# what-tinys-it.net
KiCad netlist of a schematic drawn in EAGLE
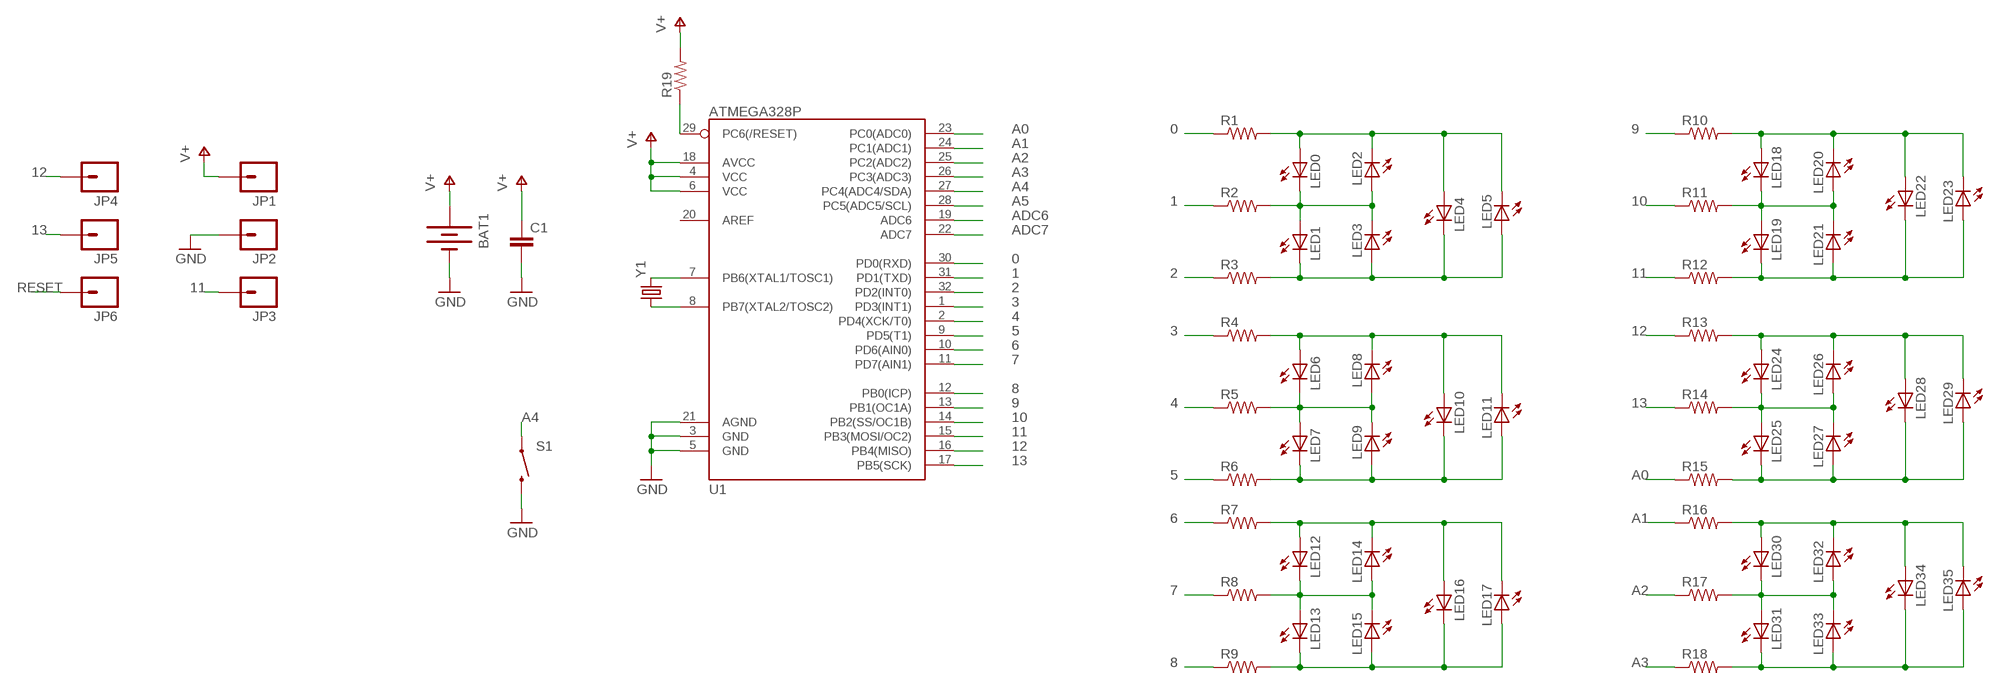
[diagram p0: schematic, sheet 1]

(export (version "E")
  (design (tool "Eeschema 10.0.6"))
  (components
    (comp (ref "BAT1")
      (value "BATTERY20SMD")
      (footprint "eagle-import:BATTCON_20MM")
      (libsource (lib "eagle-import") (part "BATTERY20SMD"))
    )
    (comp (ref "C1")
      (value "C-EUC0805")
      (footprint "eagle-import:C0805")
      (libsource (lib "eagle-import") (part "C-EUC0805"))
    )
    (comp (ref "JP1")
      (value "M01SMDNS")
      (footprint "eagle-import:1X01NS")
      (libsource (lib "eagle-import") (part "M01SMDNS"))
    )
    (comp (ref "JP2")
      (value "M01SMDNS")
      (footprint "eagle-import:1X01NS")
      (libsource (lib "eagle-import") (part "M01SMDNS"))
    )
    (comp (ref "JP3")
      (value "M01SMDNS")
      (footprint "eagle-import:1X01NS")
      (libsource (lib "eagle-import") (part "M01SMDNS"))
    )
    (comp (ref "JP4")
      (value "M01SMDNS")
      (footprint "eagle-import:1X01NS")
      (libsource (lib "eagle-import") (part "M01SMDNS"))
    )
    (comp (ref "JP5")
      (value "M01SMDNS")
      (footprint "eagle-import:1X01NS")
      (libsource (lib "eagle-import") (part "M01SMDNS"))
    )
    (comp (ref "JP6")
      (value "M01SMDNS")
      (footprint "eagle-import:1X01NS")
      (libsource (lib "eagle-import") (part "M01SMDNS"))
    )
    (comp (ref "LED0")
      (value "LEDCHIPLED_0805")
      (footprint "eagle-import:CHIPLED_0805")
      (libsource (lib "eagle-import") (part "LEDCHIPLED_0805"))
    )
    (comp (ref "LED1")
      (value "LEDCHIPLED_0805")
      (footprint "eagle-import:CHIPLED_0805")
      (libsource (lib "eagle-import") (part "LEDCHIPLED_0805"))
    )
    (comp (ref "LED2")
      (value "LEDCHIPLED_0805")
      (footprint "eagle-import:CHIPLED_0805")
      (libsource (lib "eagle-import") (part "LEDCHIPLED_0805"))
    )
    (comp (ref "LED3")
      (value "LEDCHIPLED_0805")
      (footprint "eagle-import:CHIPLED_0805")
      (libsource (lib "eagle-import") (part "LEDCHIPLED_0805"))
    )
    (comp (ref "LED4")
      (value "LEDCHIPLED_0805")
      (footprint "eagle-import:CHIPLED_0805")
      (libsource (lib "eagle-import") (part "LEDCHIPLED_0805"))
    )
    (comp (ref "LED5")
      (value "LEDCHIPLED_0805")
      (footprint "eagle-import:CHIPLED_0805")
      (libsource (lib "eagle-import") (part "LEDCHIPLED_0805"))
    )
    (comp (ref "LED6")
      (value "LEDCHIPLED_0805")
      (footprint "eagle-import:CHIPLED_0805")
      (libsource (lib "eagle-import") (part "LEDCHIPLED_0805"))
    )
    (comp (ref "LED7")
      (value "LEDCHIPLED_0805")
      (footprint "eagle-import:CHIPLED_0805")
      (libsource (lib "eagle-import") (part "LEDCHIPLED_0805"))
    )
    (comp (ref "LED8")
      (value "LEDCHIPLED_0805")
      (footprint "eagle-import:CHIPLED_0805")
      (libsource (lib "eagle-import") (part "LEDCHIPLED_0805"))
    )
    (comp (ref "LED9")
      (value "LEDCHIPLED_0805")
      (footprint "eagle-import:CHIPLED_0805")
      (libsource (lib "eagle-import") (part "LEDCHIPLED_0805"))
    )
    (comp (ref "LED10")
      (value "LEDCHIPLED_0805")
      (footprint "eagle-import:CHIPLED_0805")
      (libsource (lib "eagle-import") (part "LEDCHIPLED_0805"))
    )
    (comp (ref "LED11")
      (value "LEDCHIPLED_0805")
      (footprint "eagle-import:CHIPLED_0805")
      (libsource (lib "eagle-import") (part "LEDCHIPLED_0805"))
    )
    (comp (ref "LED12")
      (value "LEDCHIPLED_0805")
      (footprint "eagle-import:CHIPLED_0805")
      (libsource (lib "eagle-import") (part "LEDCHIPLED_0805"))
    )
    (comp (ref "LED13")
      (value "LEDCHIPLED_0805")
      (footprint "eagle-import:CHIPLED_0805")
      (libsource (lib "eagle-import") (part "LEDCHIPLED_0805"))
    )
    (comp (ref "LED14")
      (value "LEDCHIPLED_0805")
      (footprint "eagle-import:CHIPLED_0805")
      (libsource (lib "eagle-import") (part "LEDCHIPLED_0805"))
    )
    (comp (ref "LED15")
      (value "LEDCHIPLED_0805")
      (footprint "eagle-import:CHIPLED_0805")
      (libsource (lib "eagle-import") (part "LEDCHIPLED_0805"))
    )
    (comp (ref "LED16")
      (value "LEDCHIPLED_0805")
      (footprint "eagle-import:CHIPLED_0805")
      (libsource (lib "eagle-import") (part "LEDCHIPLED_0805"))
    )
    (comp (ref "LED17")
      (value "LEDCHIPLED_0805")
      (footprint "eagle-import:CHIPLED_0805")
      (libsource (lib "eagle-import") (part "LEDCHIPLED_0805"))
    )
    (comp (ref "LED18")
      (value "LEDCHIPLED_0805")
      (footprint "eagle-import:CHIPLED_0805")
      (libsource (lib "eagle-import") (part "LEDCHIPLED_0805"))
    )
    (comp (ref "LED19")
      (value "LEDCHIPLED_0805")
      (footprint "eagle-import:CHIPLED_0805")
      (libsource (lib "eagle-import") (part "LEDCHIPLED_0805"))
    )
    (comp (ref "LED20")
      (value "LEDCHIPLED_0805")
      (footprint "eagle-import:CHIPLED_0805")
      (libsource (lib "eagle-import") (part "LEDCHIPLED_0805"))
    )
    (comp (ref "LED21")
      (value "LEDCHIPLED_0805")
      (footprint "eagle-import:CHIPLED_0805")
      (libsource (lib "eagle-import") (part "LEDCHIPLED_0805"))
    )
    (comp (ref "LED22")
      (value "LEDCHIPLED_0805")
      (footprint "eagle-import:CHIPLED_0805")
      (libsource (lib "eagle-import") (part "LEDCHIPLED_0805"))
    )
    (comp (ref "LED23")
      (value "LEDCHIPLED_0805")
      (footprint "eagle-import:CHIPLED_0805")
      (libsource (lib "eagle-import") (part "LEDCHIPLED_0805"))
    )
    (comp (ref "LED24")
      (value "LEDCHIPLED_0805")
      (footprint "eagle-import:CHIPLED_0805")
      (libsource (lib "eagle-import") (part "LEDCHIPLED_0805"))
    )
    (comp (ref "LED25")
      (value "LEDCHIPLED_0805")
      (footprint "eagle-import:CHIPLED_0805")
      (libsource (lib "eagle-import") (part "LEDCHIPLED_0805"))
    )
    (comp (ref "LED26")
      (value "LEDCHIPLED_0805")
      (footprint "eagle-import:CHIPLED_0805")
      (libsource (lib "eagle-import") (part "LEDCHIPLED_0805"))
    )
    (comp (ref "LED27")
      (value "LEDCHIPLED_0805")
      (footprint "eagle-import:CHIPLED_0805")
      (libsource (lib "eagle-import") (part "LEDCHIPLED_0805"))
    )
    (comp (ref "LED28")
      (value "LEDCHIPLED_0805")
      (footprint "eagle-import:CHIPLED_0805")
      (libsource (lib "eagle-import") (part "LEDCHIPLED_0805"))
    )
    (comp (ref "LED29")
      (value "LEDCHIPLED_0805")
      (footprint "eagle-import:CHIPLED_0805")
      (libsource (lib "eagle-import") (part "LEDCHIPLED_0805"))
    )
    (comp (ref "LED30")
      (value "LEDCHIPLED_0805")
      (footprint "eagle-import:CHIPLED_0805")
      (libsource (lib "eagle-import") (part "LEDCHIPLED_0805"))
    )
    (comp (ref "LED31")
      (value "LEDCHIPLED_0805")
      (footprint "eagle-import:CHIPLED_0805")
      (libsource (lib "eagle-import") (part "LEDCHIPLED_0805"))
    )
    (comp (ref "LED32")
      (value "LEDCHIPLED_0805")
      (footprint "eagle-import:CHIPLED_0805")
      (libsource (lib "eagle-import") (part "LEDCHIPLED_0805"))
    )
    (comp (ref "LED33")
      (value "LEDCHIPLED_0805")
      (footprint "eagle-import:CHIPLED_0805")
      (libsource (lib "eagle-import") (part "LEDCHIPLED_0805"))
    )
    (comp (ref "LED34")
      (value "LEDCHIPLED_0805")
      (footprint "eagle-import:CHIPLED_0805")
      (libsource (lib "eagle-import") (part "LEDCHIPLED_0805"))
    )
    (comp (ref "LED35")
      (value "LEDCHIPLED_0805")
      (footprint "eagle-import:CHIPLED_0805")
      (libsource (lib "eagle-import") (part "LEDCHIPLED_0805"))
    )
    (comp (ref "R1")
      (value "RESISTOR0805-RES")
      (footprint "eagle-import:0805")
      (libsource (lib "eagle-import") (part "RESISTOR0805-RES"))
    )
    (comp (ref "R2")
      (value "RESISTOR0805-RES")
      (footprint "eagle-import:0805")
      (libsource (lib "eagle-import") (part "RESISTOR0805-RES"))
    )
    (comp (ref "R3")
      (value "RESISTOR0805-RES")
      (footprint "eagle-import:0805")
      (libsource (lib "eagle-import") (part "RESISTOR0805-RES"))
    )
    (comp (ref "R4")
      (value "RESISTOR0805-RES")
      (footprint "eagle-import:0805")
      (libsource (lib "eagle-import") (part "RESISTOR0805-RES"))
    )
    (comp (ref "R5")
      (value "RESISTOR0805-RES")
      (footprint "eagle-import:0805")
      (libsource (lib "eagle-import") (part "RESISTOR0805-RES"))
    )
    (comp (ref "R6")
      (value "RESISTOR0805-RES")
      (footprint "eagle-import:0805")
      (libsource (lib "eagle-import") (part "RESISTOR0805-RES"))
    )
    (comp (ref "R7")
      (value "RESISTOR0805-RES")
      (footprint "eagle-import:0805")
      (libsource (lib "eagle-import") (part "RESISTOR0805-RES"))
    )
    (comp (ref "R8")
      (value "RESISTOR0805-RES")
      (footprint "eagle-import:0805")
      (libsource (lib "eagle-import") (part "RESISTOR0805-RES"))
    )
    (comp (ref "R9")
      (value "RESISTOR0805-RES")
      (footprint "eagle-import:0805")
      (libsource (lib "eagle-import") (part "RESISTOR0805-RES"))
    )
    (comp (ref "R10")
      (value "RESISTOR0805-RES")
      (footprint "eagle-import:0805")
      (libsource (lib "eagle-import") (part "RESISTOR0805-RES"))
    )
    (comp (ref "R11")
      (value "RESISTOR0805-RES")
      (footprint "eagle-import:0805")
      (libsource (lib "eagle-import") (part "RESISTOR0805-RES"))
    )
    (comp (ref "R12")
      (value "RESISTOR0805-RES")
      (footprint "eagle-import:0805")
      (libsource (lib "eagle-import") (part "RESISTOR0805-RES"))
    )
    (comp (ref "R13")
      (value "RESISTOR0805-RES")
      (footprint "eagle-import:0805")
      (libsource (lib "eagle-import") (part "RESISTOR0805-RES"))
    )
    (comp (ref "R14")
      (value "RESISTOR0805-RES")
      (footprint "eagle-import:0805")
      (libsource (lib "eagle-import") (part "RESISTOR0805-RES"))
    )
    (comp (ref "R15")
      (value "RESISTOR0805-RES")
      (footprint "eagle-import:0805")
      (libsource (lib "eagle-import") (part "RESISTOR0805-RES"))
    )
    (comp (ref "R16")
      (value "RESISTOR0805-RES")
      (footprint "eagle-import:0805")
      (libsource (lib "eagle-import") (part "RESISTOR0805-RES"))
    )
    (comp (ref "R17")
      (value "RESISTOR0805-RES")
      (footprint "eagle-import:0805")
      (libsource (lib "eagle-import") (part "RESISTOR0805-RES"))
    )
    (comp (ref "R18")
      (value "RESISTOR0805-RES")
      (footprint "eagle-import:0805")
      (libsource (lib "eagle-import") (part "RESISTOR0805-RES"))
    )
    (comp (ref "R19")
      (value "RESISTOR0805-RES")
      (footprint "eagle-import:0805")
      (libsource (lib "eagle-import") (part "RESISTOR0805-RES"))
    )
    (comp (ref "S1")
      (value "SWITCH-MOMENTARY-2SMD-3")
      (footprint "eagle-import:TACTILE_SWITCH_SMD-3")
      (libsource (lib "eagle-import") (part "SWITCH-MOMENTARY-2SMD-3"))
    )
    (comp (ref "U1")
      (value "ATMEGA328P")
      (footprint "eagle-import:TQFP32-08")
      (libsource (lib "eagle-import") (part "ATMEGA328_SMT"))
    )
    (comp (ref "Y1")
      (value "CRYSTAL32-SMD")
      (footprint "eagle-import:CRYSTAL-32KHZ-SMD")
      (libsource (lib "eagle-import") (part "CRYSTAL32-SMD"))
    )
  )
  (nets
    (net (code "1") (name "/0") (class "Default")
      (node (ref "R1") (pin "1") (pinfunction "1_1") (pintype "passive"))
      (node (ref "U1") (pin "30") (pinfunction "PD0(RXD)_30") (pintype "bidirectional"))
    )
    (net (code "2") (name "/1") (class "Default")
      (node (ref "R2") (pin "1") (pinfunction "1_1") (pintype "passive"))
      (node (ref "U1") (pin "31") (pinfunction "PD1(TXD)_31") (pintype "bidirectional"))
    )
    (net (code "3") (name "/2") (class "Default")
      (node (ref "R3") (pin "1") (pinfunction "1_1") (pintype "passive"))
      (node (ref "U1") (pin "32") (pinfunction "PD2(INT0)_32") (pintype "bidirectional"))
    )
    (net (code "4") (name "/3") (class "Default")
      (node (ref "R4") (pin "1") (pinfunction "1_1") (pintype "passive"))
      (node (ref "U1") (pin "1") (pinfunction "PD3(INT1)_1") (pintype "bidirectional"))
    )
    (net (code "5") (name "/4") (class "Default")
      (node (ref "R5") (pin "1") (pinfunction "1_1") (pintype "passive"))
      (node (ref "U1") (pin "2") (pinfunction "PD4(XCK/T0)_2") (pintype "bidirectional"))
    )
    (net (code "6") (name "/5") (class "Default")
      (node (ref "R6") (pin "1") (pinfunction "1_1") (pintype "passive"))
      (node (ref "U1") (pin "9") (pinfunction "PD5(T1)_9") (pintype "bidirectional"))
    )
    (net (code "7") (name "/6") (class "Default")
      (node (ref "R7") (pin "1") (pinfunction "1_1") (pintype "passive"))
      (node (ref "U1") (pin "10") (pinfunction "PD6(AIN0)_10") (pintype "bidirectional"))
    )
    (net (code "8") (name "/7") (class "Default")
      (node (ref "R8") (pin "1") (pinfunction "1_1") (pintype "passive"))
      (node (ref "U1") (pin "11") (pinfunction "PD7(AIN1)_11") (pintype "bidirectional"))
    )
    (net (code "9") (name "/8") (class "Default")
      (node (ref "R9") (pin "1") (pinfunction "1_1") (pintype "passive"))
      (node (ref "U1") (pin "12") (pinfunction "PB0(ICP)_12") (pintype "bidirectional"))
    )
    (net (code "10") (name "/9") (class "Default")
      (node (ref "R10") (pin "1") (pinfunction "1_1") (pintype "passive"))
      (node (ref "U1") (pin "13") (pinfunction "PB1(OC1A)_13") (pintype "bidirectional"))
    )
    (net (code "11") (name "/10") (class "Default")
      (node (ref "R11") (pin "1") (pinfunction "1_1") (pintype "passive"))
      (node (ref "U1") (pin "14") (pinfunction "PB2(SS/OC1B)_14") (pintype "bidirectional"))
    )
    (net (code "12") (name "/11") (class "Default")
      (node (ref "JP3") (pin "1") (pinfunction "1_1") (pintype "passive"))
      (node (ref "R12") (pin "1") (pinfunction "1_1") (pintype "passive"))
      (node (ref "U1") (pin "15") (pinfunction "PB3(MOSI/OC2)_15") (pintype "bidirectional"))
    )
    (net (code "13") (name "/12") (class "Default")
      (node (ref "JP4") (pin "1") (pinfunction "1_1") (pintype "passive"))
      (node (ref "R13") (pin "1") (pinfunction "1_1") (pintype "passive"))
      (node (ref "U1") (pin "16") (pinfunction "PB4(MISO)_16") (pintype "bidirectional"))
    )
    (net (code "14") (name "/13") (class "Default")
      (node (ref "JP5") (pin "1") (pinfunction "1_1") (pintype "passive"))
      (node (ref "R14") (pin "1") (pinfunction "1_1") (pintype "passive"))
      (node (ref "U1") (pin "17") (pinfunction "PB5(SCK)_17") (pintype "bidirectional"))
    )
    (net (code "15") (name "/A0") (class "Default")
      (node (ref "R15") (pin "1") (pinfunction "1_1") (pintype "passive"))
      (node (ref "U1") (pin "23") (pinfunction "PC0(ADC0)_23") (pintype "bidirectional"))
    )
    (net (code "16") (name "/A1") (class "Default")
      (node (ref "R16") (pin "1") (pinfunction "1_1") (pintype "passive"))
      (node (ref "U1") (pin "24") (pinfunction "PC1(ADC1)_24") (pintype "bidirectional"))
    )
    (net (code "17") (name "/A2") (class "Default")
      (node (ref "R17") (pin "1") (pinfunction "1_1") (pintype "passive"))
      (node (ref "U1") (pin "25") (pinfunction "PC2(ADC2)_25") (pintype "bidirectional"))
    )
    (net (code "18") (name "/A3") (class "Default")
      (node (ref "R18") (pin "1") (pinfunction "1_1") (pintype "passive"))
      (node (ref "U1") (pin "26") (pinfunction "PC3(ADC3)_26") (pintype "bidirectional"))
    )
    (net (code "19") (name "/A4") (class "Default")
      (node (ref "S1") (pin "1") (pinfunction "1_1") (pintype "passive"))
      (node (ref "U1") (pin "27") (pinfunction "PC4(ADC4/SDA)_27") (pintype "bidirectional"))
    )
    (net (code "20") (name "/A5") (class "Default")
      (node (ref "U1") (pin "28") (pinfunction "PC5(ADC5/SCL)_28") (pintype "bidirectional"))
    )
    (net (code "21") (name "/ADC6") (class "Default")
      (node (ref "U1") (pin "19") (pinfunction "ADC6_19") (pintype "bidirectional"))
    )
    (net (code "22") (name "/ADC7") (class "Default")
      (node (ref "U1") (pin "22") (pinfunction "ADC7_22") (pintype "bidirectional"))
    )
    (net (code "23") (name "/RESET") (class "Default")
      (node (ref "JP6") (pin "1") (pinfunction "1_1") (pintype "passive"))
      (node (ref "R19") (pin "1") (pinfunction "1_1") (pintype "passive"))
      (node (ref "U1") (pin "29") (pinfunction "PC6(/RESET)_29") (pintype "bidirectional"))
    )
    (net (code "24") (name "GND") (class "Default")
      (node (ref "BAT1") (pin "2") (pinfunction "-_2") (pintype "power_in"))
      (node (ref "C1") (pin "2") (pinfunction "2_2") (pintype "passive"))
      (node (ref "JP2") (pin "1") (pinfunction "1_1") (pintype "passive"))
      (node (ref "S1") (pin "4") (pinfunction "2_4") (pintype "passive"))
      (node (ref "U1") (pin "21") (pinfunction "AGND_21") (pintype "bidirectional"))
      (node (ref "U1") (pin "3") (pinfunction "GND_3") (pintype "bidirectional"))
      (node (ref "U1") (pin "5") (pinfunction "GND_5") (pintype "bidirectional"))
    )
    (net (code "25") (name "Net-(LED0-PadA)") (class "Default")
      (node (ref "LED0") (pin "A") (pinfunction "A_A") (pintype "passive"))
      (node (ref "LED2") (pin "C") (pinfunction "C_C") (pintype "passive"))
      (node (ref "LED4") (pin "A") (pinfunction "A_A") (pintype "passive"))
      (node (ref "LED5") (pin "C") (pinfunction "C_C") (pintype "passive"))
      (node (ref "R1") (pin "2") (pinfunction "2_2") (pintype "passive"))
    )
    (net (code "26") (name "Net-(LED0-PadC)") (class "Default")
      (node (ref "LED0") (pin "C") (pinfunction "C_C") (pintype "passive"))
      (node (ref "LED1") (pin "A") (pinfunction "A_A") (pintype "passive"))
      (node (ref "LED2") (pin "A") (pinfunction "A_A") (pintype "passive"))
      (node (ref "LED3") (pin "C") (pinfunction "C_C") (pintype "passive"))
      (node (ref "R2") (pin "2") (pinfunction "2_2") (pintype "passive"))
    )
    (net (code "27") (name "Net-(LED1-PadC)") (class "Default")
      (node (ref "LED1") (pin "C") (pinfunction "C_C") (pintype "passive"))
      (node (ref "LED3") (pin "A") (pinfunction "A_A") (pintype "passive"))
      (node (ref "LED4") (pin "C") (pinfunction "C_C") (pintype "passive"))
      (node (ref "LED5") (pin "A") (pinfunction "A_A") (pintype "passive"))
      (node (ref "R3") (pin "2") (pinfunction "2_2") (pintype "passive"))
    )
    (net (code "28") (name "Net-(LED6-PadC)") (class "Default")
      (node (ref "LED6") (pin "C") (pinfunction "C_C") (pintype "passive"))
      (node (ref "LED7") (pin "A") (pinfunction "A_A") (pintype "passive"))
      (node (ref "LED8") (pin "A") (pinfunction "A_A") (pintype "passive"))
      (node (ref "LED9") (pin "C") (pinfunction "C_C") (pintype "passive"))
      (node (ref "R5") (pin "2") (pinfunction "2_2") (pintype "passive"))
    )
    (net (code "29") (name "Net-(LED10-PadA)") (class "Default")
      (node (ref "LED10") (pin "A") (pinfunction "A_A") (pintype "passive"))
      (node (ref "LED11") (pin "C") (pinfunction "C_C") (pintype "passive"))
      (node (ref "LED6") (pin "A") (pinfunction "A_A") (pintype "passive"))
      (node (ref "LED8") (pin "C") (pinfunction "C_C") (pintype "passive"))
      (node (ref "R4") (pin "2") (pinfunction "2_2") (pintype "passive"))
    )
    (net (code "30") (name "Net-(LED10-PadC)") (class "Default")
      (node (ref "LED10") (pin "C") (pinfunction "C_C") (pintype "passive"))
      (node (ref "LED11") (pin "A") (pinfunction "A_A") (pintype "passive"))
      (node (ref "LED7") (pin "C") (pinfunction "C_C") (pintype "passive"))
      (node (ref "LED9") (pin "A") (pinfunction "A_A") (pintype "passive"))
      (node (ref "R6") (pin "2") (pinfunction "2_2") (pintype "passive"))
    )
    (net (code "31") (name "Net-(LED12-PadA)") (class "Default")
      (node (ref "LED12") (pin "A") (pinfunction "A_A") (pintype "passive"))
      (node (ref "LED14") (pin "C") (pinfunction "C_C") (pintype "passive"))
      (node (ref "LED16") (pin "A") (pinfunction "A_A") (pintype "passive"))
      (node (ref "LED17") (pin "C") (pinfunction "C_C") (pintype "passive"))
      (node (ref "R7") (pin "2") (pinfunction "2_2") (pintype "passive"))
    )
    (net (code "32") (name "Net-(LED12-PadC)") (class "Default")
      (node (ref "LED12") (pin "C") (pinfunction "C_C") (pintype "passive"))
      (node (ref "LED13") (pin "A") (pinfunction "A_A") (pintype "passive"))
      (node (ref "LED14") (pin "A") (pinfunction "A_A") (pintype "passive"))
      (node (ref "LED15") (pin "C") (pinfunction "C_C") (pintype "passive"))
      (node (ref "R8") (pin "2") (pinfunction "2_2") (pintype "passive"))
    )
    (net (code "33") (name "Net-(LED13-PadC)") (class "Default")
      (node (ref "LED13") (pin "C") (pinfunction "C_C") (pintype "passive"))
      (node (ref "LED15") (pin "A") (pinfunction "A_A") (pintype "passive"))
      (node (ref "LED16") (pin "C") (pinfunction "C_C") (pintype "passive"))
      (node (ref "LED17") (pin "A") (pinfunction "A_A") (pintype "passive"))
      (node (ref "R9") (pin "2") (pinfunction "2_2") (pintype "passive"))
    )
    (net (code "34") (name "Net-(LED18-PadA)") (class "Default")
      (node (ref "LED18") (pin "A") (pinfunction "A_A") (pintype "passive"))
      (node (ref "LED20") (pin "C") (pinfunction "C_C") (pintype "passive"))
      (node (ref "LED22") (pin "A") (pinfunction "A_A") (pintype "passive"))
      (node (ref "LED23") (pin "C") (pinfunction "C_C") (pintype "passive"))
      (node (ref "R10") (pin "2") (pinfunction "2_2") (pintype "passive"))
    )
    (net (code "35") (name "Net-(LED18-PadC)") (class "Default")
      (node (ref "LED18") (pin "C") (pinfunction "C_C") (pintype "passive"))
      (node (ref "LED19") (pin "A") (pinfunction "A_A") (pintype "passive"))
      (node (ref "LED20") (pin "A") (pinfunction "A_A") (pintype "passive"))
      (node (ref "LED21") (pin "C") (pinfunction "C_C") (pintype "passive"))
      (node (ref "R11") (pin "2") (pinfunction "2_2") (pintype "passive"))
    )
    (net (code "36") (name "Net-(LED19-PadC)") (class "Default")
      (node (ref "LED19") (pin "C") (pinfunction "C_C") (pintype "passive"))
      (node (ref "LED21") (pin "A") (pinfunction "A_A") (pintype "passive"))
      (node (ref "LED22") (pin "C") (pinfunction "C_C") (pintype "passive"))
      (node (ref "LED23") (pin "A") (pinfunction "A_A") (pintype "passive"))
      (node (ref "R12") (pin "2") (pinfunction "2_2") (pintype "passive"))
    )
    (net (code "37") (name "Net-(LED24-PadA)") (class "Default")
      (node (ref "LED24") (pin "A") (pinfunction "A_A") (pintype "passive"))
      (node (ref "LED26") (pin "C") (pinfunction "C_C") (pintype "passive"))
      (node (ref "LED28") (pin "A") (pinfunction "A_A") (pintype "passive"))
      (node (ref "LED29") (pin "C") (pinfunction "C_C") (pintype "passive"))
      (node (ref "R13") (pin "2") (pinfunction "2_2") (pintype "passive"))
    )
    (net (code "38") (name "Net-(LED24-PadC)") (class "Default")
      (node (ref "LED24") (pin "C") (pinfunction "C_C") (pintype "passive"))
      (node (ref "LED25") (pin "A") (pinfunction "A_A") (pintype "passive"))
      (node (ref "LED26") (pin "A") (pinfunction "A_A") (pintype "passive"))
      (node (ref "LED27") (pin "C") (pinfunction "C_C") (pintype "passive"))
      (node (ref "R14") (pin "2") (pinfunction "2_2") (pintype "passive"))
    )
    (net (code "39") (name "Net-(LED25-PadC)") (class "Default")
      (node (ref "LED25") (pin "C") (pinfunction "C_C") (pintype "passive"))
      (node (ref "LED27") (pin "A") (pinfunction "A_A") (pintype "passive"))
      (node (ref "LED28") (pin "C") (pinfunction "C_C") (pintype "passive"))
      (node (ref "LED29") (pin "A") (pinfunction "A_A") (pintype "passive"))
      (node (ref "R15") (pin "2") (pinfunction "2_2") (pintype "passive"))
    )
    (net (code "40") (name "Net-(LED30-PadA)") (class "Default")
      (node (ref "LED30") (pin "A") (pinfunction "A_A") (pintype "passive"))
      (node (ref "LED32") (pin "C") (pinfunction "C_C") (pintype "passive"))
      (node (ref "LED34") (pin "A") (pinfunction "A_A") (pintype "passive"))
      (node (ref "LED35") (pin "C") (pinfunction "C_C") (pintype "passive"))
      (node (ref "R16") (pin "2") (pinfunction "2_2") (pintype "passive"))
    )
    (net (code "41") (name "Net-(LED30-PadC)") (class "Default")
      (node (ref "LED30") (pin "C") (pinfunction "C_C") (pintype "passive"))
      (node (ref "LED31") (pin "A") (pinfunction "A_A") (pintype "passive"))
      (node (ref "LED32") (pin "A") (pinfunction "A_A") (pintype "passive"))
      (node (ref "LED33") (pin "C") (pinfunction "C_C") (pintype "passive"))
      (node (ref "R17") (pin "2") (pinfunction "2_2") (pintype "passive"))
    )
    (net (code "42") (name "Net-(LED31-PadC)") (class "Default")
      (node (ref "LED31") (pin "C") (pinfunction "C_C") (pintype "passive"))
      (node (ref "LED33") (pin "A") (pinfunction "A_A") (pintype "passive"))
      (node (ref "LED34") (pin "C") (pinfunction "C_C") (pintype "passive"))
      (node (ref "LED35") (pin "A") (pinfunction "A_A") (pintype "passive"))
      (node (ref "R18") (pin "2") (pinfunction "2_2") (pintype "passive"))
    )
    (net (code "43") (name "Net-(U1-PB6(XTAL1{slash}TOSC1))") (class "Default")
      (node (ref "U1") (pin "7") (pinfunction "PB6(XTAL1/TOSC1)_7") (pintype "bidirectional"))
      (node (ref "Y1") (pin "X2") (pinfunction "2_X2") (pintype "passive"))
    )
    (net (code "44") (name "Net-(U1-PB7(XTAL2{slash}TOSC2))") (class "Default")
      (node (ref "U1") (pin "8") (pinfunction "PB7(XTAL2/TOSC2)_8") (pintype "bidirectional"))
      (node (ref "Y1") (pin "X1") (pinfunction "1_X1") (pintype "passive"))
    )
    (net (code "45") (name "V+") (class "Default")
      (node (ref "BAT1") (pin "1") (pinfunction "+_1") (pintype "power_in"))
      (node (ref "C1") (pin "1") (pinfunction "1_1") (pintype "passive"))
      (node (ref "JP1") (pin "1") (pinfunction "1_1") (pintype "passive"))
      (node (ref "R19") (pin "2") (pinfunction "2_2") (pintype "passive"))
      (node (ref "U1") (pin "18") (pinfunction "AVCC_18") (pintype "bidirectional"))
      (node (ref "U1") (pin "4") (pinfunction "VCC_4") (pintype "bidirectional"))
      (node (ref "U1") (pin "6") (pinfunction "VCC_6") (pintype "bidirectional"))
    )
    (net (code "46") (name "unconnected-(U1-AREF-Pad20)") (class "Default")
      (node (ref "U1") (pin "20") (pinfunction "AREF_20") (pintype "bidirectional"))
    )
  )
)
